# 8_Channel_Relay_Board_Omron.net
KiCad netlist of a schematic drawn in EasyEDA
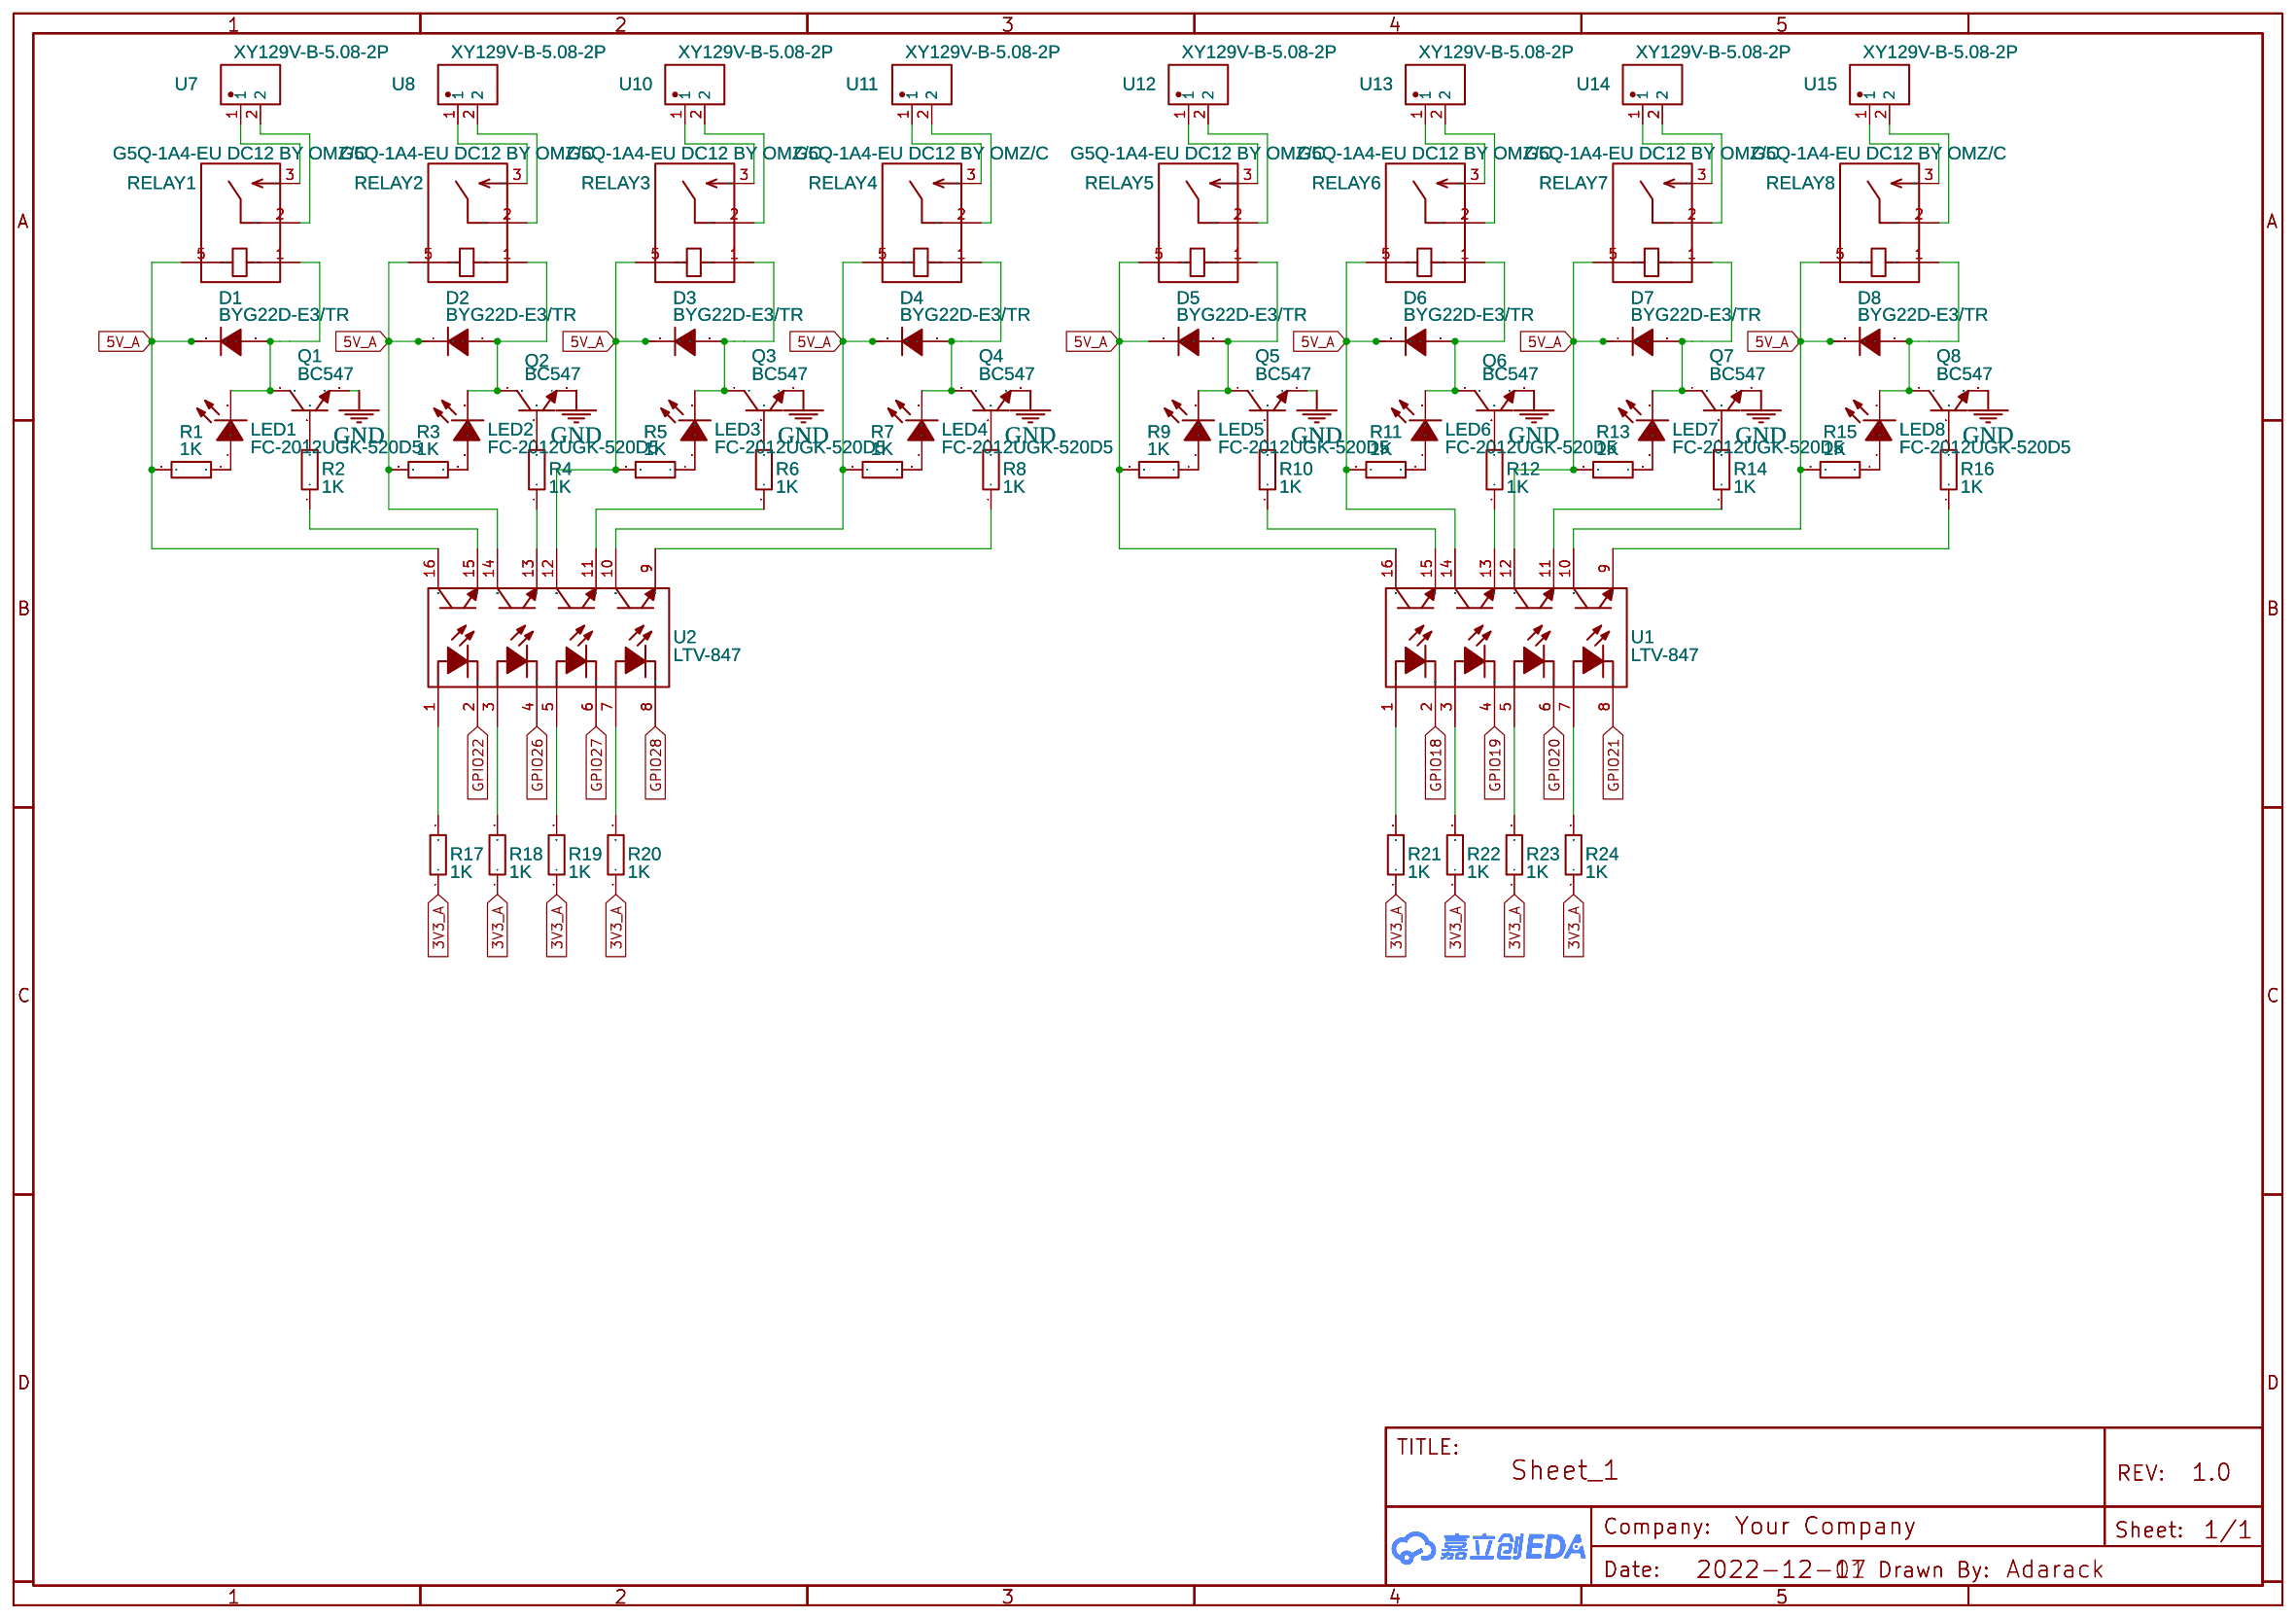
[diagram p0: Relay Section]
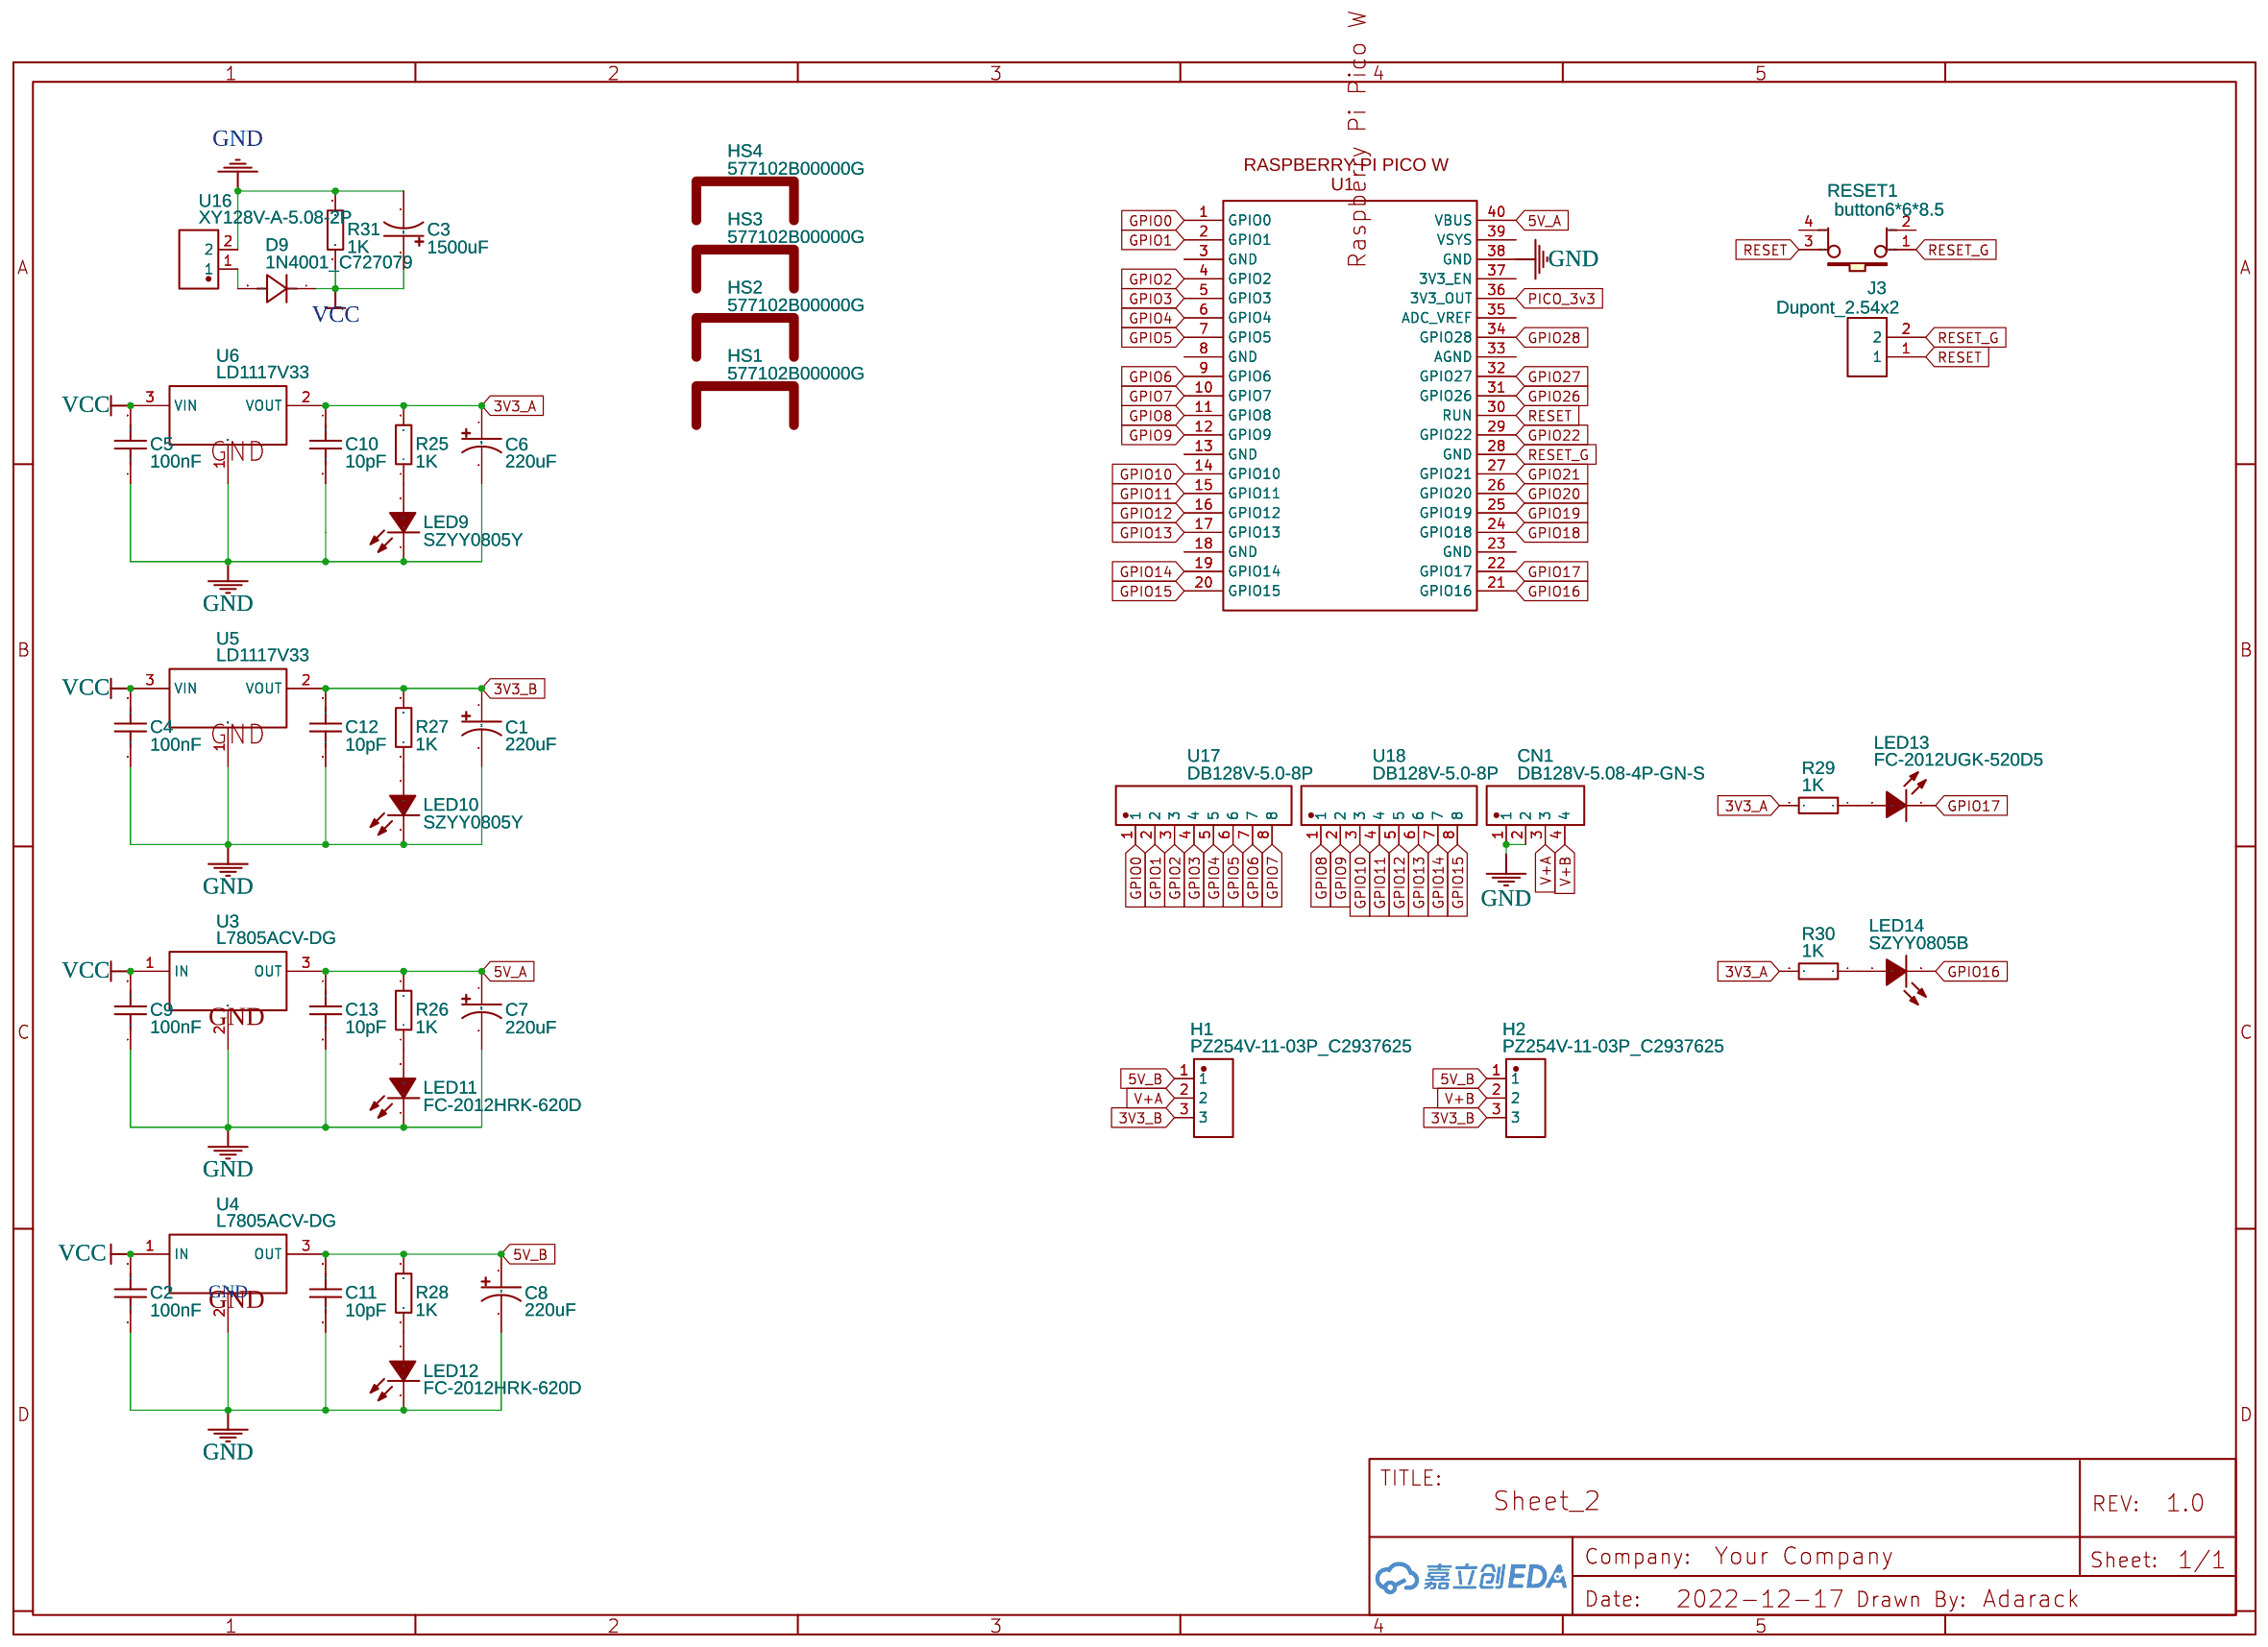
[diagram p1: Pico W Section]

(export (version "E")
  (design (tool "Eeschema 10.0.6"))
  (components
    (comp (ref "D1")
      (value "BYG22D-E3/TR")
      (fields (field (name "BOM_Supplier Part") "C52782"))
      (libsource (lib "") (part "BYG22D-E3/TR"))
    )
    (comp (ref "D2")
      (value "BYG22D-E3/TR")
      (fields (field (name "BOM_Supplier Part") "C52782"))
      (libsource (lib "") (part "BYG22D-E3/TR"))
    )
    (comp (ref "D3")
      (value "BYG22D-E3/TR")
      (fields (field (name "BOM_Supplier Part") "C52782"))
      (libsource (lib "") (part "BYG22D-E3/TR"))
    )
    (comp (ref "D4")
      (value "BYG22D-E3/TR")
      (fields (field (name "BOM_Supplier Part") "C52782"))
      (libsource (lib "") (part "BYG22D-E3/TR"))
    )
    (comp (ref "D5")
      (value "BYG22D-E3/TR")
      (fields (field (name "BOM_Supplier Part") "C52782"))
      (libsource (lib "") (part "BYG22D-E3/TR"))
    )
    (comp (ref "D6")
      (value "BYG22D-E3/TR")
      (fields (field (name "BOM_Supplier Part") "C52782"))
      (libsource (lib "") (part "BYG22D-E3/TR"))
    )
    (comp (ref "D7")
      (value "BYG22D-E3/TR")
      (fields (field (name "BOM_Supplier Part") "C52782"))
      (libsource (lib "") (part "BYG22D-E3/TR"))
    )
    (comp (ref "D8")
      (value "BYG22D-E3/TR")
      (fields (field (name "BOM_Supplier Part") "C52782"))
      (libsource (lib "") (part "BYG22D-E3/TR"))
    )
    (comp (ref "LED1")
      (value "FC-2012UGK-520D5")
      (fields (field (name "BOM_Manufacturer Part") "NCD0805G1") (field (name "BOM_Supplier Part") "C84260"))
      (libsource (lib "") (part "FC-2012UGK-520D5"))
    )
    (comp (ref "LED2")
      (value "FC-2012UGK-520D5")
      (fields (field (name "BOM_Manufacturer Part") "NCD0805G1") (field (name "BOM_Supplier Part") "C84260"))
      (libsource (lib "") (part "FC-2012UGK-520D5"))
    )
    (comp (ref "LED3")
      (value "FC-2012UGK-520D5")
      (fields (field (name "BOM_Manufacturer Part") "NCD0805G1") (field (name "BOM_Supplier Part") "C84260"))
      (libsource (lib "") (part "FC-2012UGK-520D5"))
    )
    (comp (ref "LED4")
      (value "FC-2012UGK-520D5")
      (fields (field (name "BOM_Manufacturer Part") "NCD0805G1") (field (name "BOM_Supplier Part") "C84260"))
      (libsource (lib "") (part "FC-2012UGK-520D5"))
    )
    (comp (ref "LED5")
      (value "FC-2012UGK-520D5")
      (fields (field (name "BOM_Manufacturer Part") "NCD0805G1") (field (name "BOM_Supplier Part") "C84260"))
      (libsource (lib "") (part "FC-2012UGK-520D5"))
    )
    (comp (ref "LED6")
      (value "FC-2012UGK-520D5")
      (fields (field (name "BOM_Manufacturer Part") "NCD0805G1") (field (name "BOM_Supplier Part") "C84260"))
      (libsource (lib "") (part "FC-2012UGK-520D5"))
    )
    (comp (ref "LED7")
      (value "FC-2012UGK-520D5")
      (fields (field (name "BOM_Manufacturer Part") "NCD0805G1") (field (name "BOM_Supplier Part") "C84260"))
      (libsource (lib "") (part "FC-2012UGK-520D5"))
    )
    (comp (ref "LED8")
      (value "FC-2012UGK-520D5")
      (fields (field (name "BOM_Manufacturer Part") "NCD0805G1") (field (name "BOM_Supplier Part") "C84260"))
      (libsource (lib "") (part "FC-2012UGK-520D5"))
    )
    (comp (ref "Q1")
      (value "BC547")
      (fields (field (name "BOM_Supplier Part") "C2910381"))
      (libsource (lib "") (part "BC547"))
    )
    (comp (ref "Q2")
      (value "BC547")
      (fields (field (name "BOM_Supplier Part") "C2910381"))
      (libsource (lib "") (part "BC547"))
    )
    (comp (ref "Q3")
      (value "BC547")
      (fields (field (name "BOM_Supplier Part") "C2910381"))
      (libsource (lib "") (part "BC547"))
    )
    (comp (ref "Q4")
      (value "BC547")
      (fields (field (name "BOM_Supplier Part") "C2910381"))
      (libsource (lib "") (part "BC547"))
    )
    (comp (ref "Q5")
      (value "BC547")
      (fields (field (name "BOM_Supplier Part") "C2910381"))
      (libsource (lib "") (part "BC547"))
    )
    (comp (ref "Q6")
      (value "BC547")
      (fields (field (name "BOM_Supplier Part") "C2910381"))
      (libsource (lib "") (part "BC547"))
    )
    (comp (ref "Q7")
      (value "BC547")
      (fields (field (name "BOM_Supplier Part") "C2910381"))
      (libsource (lib "") (part "BC547"))
    )
    (comp (ref "Q8")
      (value "BC547")
      (fields (field (name "BOM_Supplier Part") "C2910381"))
      (libsource (lib "") (part "BC547"))
    )
    (comp (ref "R1")
      (value "1K")
      (fields
        (field (name "BOM_Manufacturer Part") "RC0805FR-071KL")
        (field (name "BOM_Supplier Part") "C95781")
      )
      (libsource (lib "") (part "RC0805FR-071KL_1"))
    )
    (comp (ref "R2")
      (value "1K")
      (fields
        (field (name "BOM_Manufacturer Part") "RC0805FR-071KL")
        (field (name "BOM_Supplier Part") "C95781")
      )
      (libsource (lib "") (part "RC0805FR-071KL"))
    )
    (comp (ref "R3")
      (value "1K")
      (fields
        (field (name "BOM_Manufacturer Part") "RC0805FR-071KL")
        (field (name "BOM_Supplier Part") "C95781")
      )
      (libsource (lib "") (part "RC0805FR-071KL_1"))
    )
    (comp (ref "R4")
      (value "1K")
      (fields
        (field (name "BOM_Manufacturer Part") "RC0805FR-071KL")
        (field (name "BOM_Supplier Part") "C95781")
      )
      (libsource (lib "") (part "RC0805FR-071KL"))
    )
    (comp (ref "R5")
      (value "1K")
      (fields
        (field (name "BOM_Manufacturer Part") "RC0805FR-071KL")
        (field (name "BOM_Supplier Part") "C95781")
      )
      (libsource (lib "") (part "RC0805FR-071KL_1"))
    )
    (comp (ref "R6")
      (value "1K")
      (fields
        (field (name "BOM_Manufacturer Part") "RC0805FR-071KL")
        (field (name "BOM_Supplier Part") "C95781")
      )
      (libsource (lib "") (part "RC0805FR-071KL"))
    )
    (comp (ref "R7")
      (value "1K")
      (fields
        (field (name "BOM_Manufacturer Part") "RC0805FR-071KL")
        (field (name "BOM_Supplier Part") "C95781")
      )
      (libsource (lib "") (part "RC0805FR-071KL_1"))
    )
    (comp (ref "R8")
      (value "1K")
      (fields
        (field (name "BOM_Manufacturer Part") "RC0805FR-071KL")
        (field (name "BOM_Supplier Part") "C95781")
      )
      (libsource (lib "") (part "RC0805FR-071KL"))
    )
    (comp (ref "R9")
      (value "1K")
      (fields
        (field (name "BOM_Manufacturer Part") "RC0805FR-071KL")
        (field (name "BOM_Supplier Part") "C95781")
      )
      (libsource (lib "") (part "RC0805FR-071KL_1"))
    )
    (comp (ref "R10")
      (value "1K")
      (fields
        (field (name "BOM_Manufacturer Part") "RC0805FR-071KL")
        (field (name "BOM_Supplier Part") "C95781")
      )
      (libsource (lib "") (part "RC0805FR-071KL"))
    )
    (comp (ref "R11")
      (value "1K")
      (fields
        (field (name "BOM_Manufacturer Part") "RC0805FR-071KL")
        (field (name "BOM_Supplier Part") "C95781")
      )
      (libsource (lib "") (part "RC0805FR-071KL_1"))
    )
    (comp (ref "R12")
      (value "1K")
      (fields
        (field (name "BOM_Manufacturer Part") "RC0805FR-071KL")
        (field (name "BOM_Supplier Part") "C95781")
      )
      (libsource (lib "") (part "RC0805FR-071KL"))
    )
    (comp (ref "R13")
      (value "1K")
      (fields
        (field (name "BOM_Manufacturer Part") "RC0805FR-071KL")
        (field (name "BOM_Supplier Part") "C95781")
      )
      (libsource (lib "") (part "RC0805FR-071KL_1"))
    )
    (comp (ref "R14")
      (value "1K")
      (fields
        (field (name "BOM_Manufacturer Part") "RC0805FR-071KL")
        (field (name "BOM_Supplier Part") "C95781")
      )
      (libsource (lib "") (part "RC0805FR-071KL"))
    )
    (comp (ref "R15")
      (value "1K")
      (fields
        (field (name "BOM_Manufacturer Part") "RC0805FR-071KL")
        (field (name "BOM_Supplier Part") "C95781")
      )
      (libsource (lib "") (part "RC0805FR-071KL_1"))
    )
    (comp (ref "R16")
      (value "1K")
      (fields
        (field (name "BOM_Manufacturer Part") "RC0805FR-071KL")
        (field (name "BOM_Supplier Part") "C95781")
      )
      (libsource (lib "") (part "RC0805FR-071KL"))
    )
    (comp (ref "R17")
      (value "1K")
      (fields
        (field (name "BOM_Manufacturer Part") "RC0805FR-071KL")
        (field (name "BOM_Supplier Part") "C95781")
      )
      (libsource (lib "") (part "RC0805FR-071KL"))
    )
    (comp (ref "R18")
      (value "1K")
      (fields
        (field (name "BOM_Manufacturer Part") "RC0805FR-071KL")
        (field (name "BOM_Supplier Part") "C95781")
      )
      (libsource (lib "") (part "RC0805FR-071KL"))
    )
    (comp (ref "R19")
      (value "1K")
      (fields
        (field (name "BOM_Manufacturer Part") "RC0805FR-071KL")
        (field (name "BOM_Supplier Part") "C95781")
      )
      (libsource (lib "") (part "RC0805FR-071KL"))
    )
    (comp (ref "R20")
      (value "1K")
      (fields
        (field (name "BOM_Manufacturer Part") "RC0805FR-071KL")
        (field (name "BOM_Supplier Part") "C95781")
      )
      (libsource (lib "") (part "RC0805FR-071KL"))
    )
    (comp (ref "R21")
      (value "1K")
      (fields
        (field (name "BOM_Manufacturer Part") "RC0805FR-071KL")
        (field (name "BOM_Supplier Part") "C95781")
      )
      (libsource (lib "") (part "RC0805FR-071KL"))
    )
    (comp (ref "R22")
      (value "1K")
      (fields
        (field (name "BOM_Manufacturer Part") "RC0805FR-071KL")
        (field (name "BOM_Supplier Part") "C95781")
      )
      (libsource (lib "") (part "RC0805FR-071KL"))
    )
    (comp (ref "R23")
      (value "1K")
      (fields
        (field (name "BOM_Manufacturer Part") "RC0805FR-071KL")
        (field (name "BOM_Supplier Part") "C95781")
      )
      (libsource (lib "") (part "RC0805FR-071KL"))
    )
    (comp (ref "R24")
      (value "1K")
      (fields
        (field (name "BOM_Manufacturer Part") "RC0805FR-071KL")
        (field (name "BOM_Supplier Part") "C95781")
      )
      (libsource (lib "") (part "RC0805FR-071KL"))
    )
    (comp (ref "RELAY1")
      (value "G5Q-1A4-EU DC12 BY OMZ/C")
      (fields (field (name "BOM_Supplier Part") "C726027"))
      (libsource (lib "") (part "G5Q-1A4-EU DC12 BY OMZ/C"))
    )
    (comp (ref "RELAY2")
      (value "G5Q-1A4-EU DC12 BY OMZ/C")
      (fields (field (name "BOM_Supplier Part") "C726027"))
      (libsource (lib "") (part "G5Q-1A4-EU DC12 BY OMZ/C"))
    )
    (comp (ref "RELAY3")
      (value "G5Q-1A4-EU DC12 BY OMZ/C")
      (fields (field (name "BOM_Supplier Part") "C726027"))
      (libsource (lib "") (part "G5Q-1A4-EU DC12 BY OMZ/C"))
    )
    (comp (ref "RELAY4")
      (value "G5Q-1A4-EU DC12 BY OMZ/C")
      (fields (field (name "BOM_Supplier Part") "C726027"))
      (libsource (lib "") (part "G5Q-1A4-EU DC12 BY OMZ/C"))
    )
    (comp (ref "RELAY5")
      (value "G5Q-1A4-EU DC12 BY OMZ/C")
      (fields (field (name "BOM_Supplier Part") "C726027"))
      (libsource (lib "") (part "G5Q-1A4-EU DC12 BY OMZ/C"))
    )
    (comp (ref "RELAY6")
      (value "G5Q-1A4-EU DC12 BY OMZ/C")
      (fields (field (name "BOM_Supplier Part") "C726027"))
      (libsource (lib "") (part "G5Q-1A4-EU DC12 BY OMZ/C"))
    )
    (comp (ref "RELAY7")
      (value "G5Q-1A4-EU DC12 BY OMZ/C")
      (fields (field (name "BOM_Supplier Part") "C726027"))
      (libsource (lib "") (part "G5Q-1A4-EU DC12 BY OMZ/C"))
    )
    (comp (ref "RELAY8")
      (value "G5Q-1A4-EU DC12 BY OMZ/C")
      (fields (field (name "BOM_Supplier Part") "C726027"))
      (libsource (lib "") (part "G5Q-1A4-EU DC12 BY OMZ/C"))
    )
    (comp (ref "U1")
      (value "LTV-847")
      (fields (field (name "BOM_Supplier Part") "C10794"))
      (libsource (lib "") (part "LTV-847"))
    )
    (comp (ref "U2")
      (value "LTV-847")
      (fields (field (name "BOM_Supplier Part") "C10794"))
      (libsource (lib "") (part "LTV-847"))
    )
    (comp (ref "U7")
      (value "XY129V-B-5.08-2P")
      (fields (field (name "BOM_Supplier Part") "C557671"))
      (libsource (lib "") (part "XY129V-B-5.08-2P"))
    )
    (comp (ref "U8")
      (value "XY129V-B-5.08-2P")
      (fields (field (name "BOM_Supplier Part") "C557671"))
      (libsource (lib "") (part "XY129V-B-5.08-2P"))
    )
    (comp (ref "U10")
      (value "XY129V-B-5.08-2P")
      (fields (field (name "BOM_Supplier Part") "C557671"))
      (libsource (lib "") (part "XY129V-B-5.08-2P"))
    )
    (comp (ref "U11")
      (value "XY129V-B-5.08-2P")
      (fields (field (name "BOM_Supplier Part") "C557671"))
      (libsource (lib "") (part "XY129V-B-5.08-2P"))
    )
    (comp (ref "U12")
      (value "XY129V-B-5.08-2P")
      (fields (field (name "BOM_Supplier Part") "C557671"))
      (libsource (lib "") (part "XY129V-B-5.08-2P"))
    )
    (comp (ref "U13")
      (value "XY129V-B-5.08-2P")
      (fields (field (name "BOM_Supplier Part") "C557671"))
      (libsource (lib "") (part "XY129V-B-5.08-2P"))
    )
    (comp (ref "U14")
      (value "XY129V-B-5.08-2P")
      (fields (field (name "BOM_Supplier Part") "C557671"))
      (libsource (lib "") (part "XY129V-B-5.08-2P"))
    )
    (comp (ref "U15")
      (value "XY129V-B-5.08-2P")
      (fields (field (name "BOM_Supplier Part") "C557671"))
      (libsource (lib "") (part "XY129V-B-5.08-2P"))
    )
    (comp (ref "C1")
      (value "220uF")
      (fields
        (field (name "BOM_Manufacturer Part") "EEUFS0J221")
        (field (name "BOM_Supplier Part") "C407962")
      )
      (libsource (lib "") (part "EEUFS0J221"))
    )
    (comp (ref "C2")
      (value "100nF")
      (fields
        (field (name "BOM_Manufacturer Part") "CC0805KRX7R8BB104")
        (field (name "BOM_Supplier Part") "C519981")
      )
      (libsource (lib "") (part "CC0805KRX7R8BB104"))
    )
    (comp (ref "C3")
      (value "1500uF")
      (fields
        (field (name "BOM_Manufacturer Part") "EGF158M1VI25RRSHP")
        (field (name "BOM_Supplier Part") "C238296")
      )
      (libsource (lib "") (part "EGF158M1VI25RRSHP"))
    )
    (comp (ref "C4")
      (value "100nF")
      (fields
        (field (name "BOM_Manufacturer Part") "CC0805KRX7R8BB104")
        (field (name "BOM_Supplier Part") "C519981")
      )
      (libsource (lib "") (part "CC0805KRX7R8BB104"))
    )
    (comp (ref "C5")
      (value "100nF")
      (fields
        (field (name "BOM_Manufacturer Part") "CC0805KRX7R8BB104")
        (field (name "BOM_Supplier Part") "C519981")
      )
      (libsource (lib "") (part "CC0805KRX7R8BB104"))
    )
    (comp (ref "C6")
      (value "220uF")
      (fields
        (field (name "BOM_Manufacturer Part") "EEUFS0J221")
        (field (name "BOM_Supplier Part") "C407962")
      )
      (libsource (lib "") (part "EEUFS0J221"))
    )
    (comp (ref "C7")
      (value "220uF")
      (fields
        (field (name "BOM_Manufacturer Part") "EEUFS0J221")
        (field (name "BOM_Supplier Part") "C407962")
      )
      (libsource (lib "") (part "EEUFS0J221"))
    )
    (comp (ref "C8")
      (value "220uF")
      (fields
        (field (name "BOM_Manufacturer Part") "EEUFS0J221")
        (field (name "BOM_Supplier Part") "C407962")
      )
      (libsource (lib "") (part "EEUFS0J221_1"))
    )
    (comp (ref "C9")
      (value "100nF")
      (fields
        (field (name "BOM_Manufacturer Part") "CC0805KRX7R8BB104")
        (field (name "BOM_Supplier Part") "C519981")
      )
      (libsource (lib "") (part "CC0805KRX7R8BB104"))
    )
    (comp (ref "C10")
      (value "10pF")
      (fields
        (field (name "BOM_Manufacturer Part") "0805CG100J500NT")
        (field (name "BOM_Supplier Part") "C157608")
      )
      (libsource (lib "") (part "0805CG100J500NT"))
    )
    (comp (ref "C11")
      (value "10pF")
      (fields
        (field (name "BOM_Manufacturer Part") "0805CG100J500NT")
        (field (name "BOM_Supplier Part") "C157608")
      )
      (libsource (lib "") (part "0805CG100J500NT"))
    )
    (comp (ref "C12")
      (value "10pF")
      (fields
        (field (name "BOM_Manufacturer Part") "0805CG100J500NT")
        (field (name "BOM_Supplier Part") "C157608")
      )
      (libsource (lib "") (part "0805CG100J500NT"))
    )
    (comp (ref "C13")
      (value "10pF")
      (fields
        (field (name "BOM_Manufacturer Part") "0805CG100J500NT")
        (field (name "BOM_Supplier Part") "C157608")
      )
      (libsource (lib "") (part "0805CG100J500NT"))
    )
    (comp (ref "CN1")
      (value "DB128V-5.08-4P-GN-S")
      (fields (field (name "BOM_Supplier Part") "C2915641"))
      (libsource (lib "") (part "DB128V-5.08-4P-GN-S"))
    )
    (comp (ref "D9")
      (value "1N4001_C727079")
      (fields (field (name "BOM_Manufacturer Part") "1N4001") (field (name "BOM_Supplier Part") "C727079"))
      (libsource (lib "") (part "1N4001_C727079"))
    )
    (comp (ref "H1")
      (value "PZ254V-11-03P_C2937625")
      (fields
        (field (name "BOM_Manufacturer Part") "PZ254V-11-03P")
        (field (name "BOM_Supplier Part") "C2937625")
      )
      (libsource (lib "") (part "PZ254V-11-03P_C2937625"))
    )
    (comp (ref "H2")
      (value "PZ254V-11-03P_C2937625")
      (fields
        (field (name "BOM_Manufacturer Part") "PZ254V-11-03P")
        (field (name "BOM_Supplier Part") "C2937625")
      )
      (libsource (lib "") (part "PZ254V-11-03P_C2937625"))
    )
    (comp (ref "HS1")
      (value "577102B00000G")
      (fields (field (name "BOM_Supplier Part") "532-577102B00"))
      (libsource (lib "") (part "577102B00000G"))
    )
    (comp (ref "HS2")
      (value "577102B00000G")
      (fields (field (name "BOM_Supplier Part") "532-577102B00"))
      (libsource (lib "") (part "577102B00000G"))
    )
    (comp (ref "HS3")
      (value "577102B00000G")
      (fields (field (name "BOM_Supplier Part") "532-577102B00"))
      (libsource (lib "") (part "577102B00000G"))
    )
    (comp (ref "HS4")
      (value "577102B00000G")
      (fields (field (name "BOM_Supplier Part") "532-577102B00"))
      (libsource (lib "") (part "577102B00000G"))
    )
    (comp (ref "J3") (value "Dupont_2.54x2") (libsource (lib "") (part "Dupont_2.54x2")))
    (comp (ref "LED9")
      (value "SZYY0805Y")
      (fields (field (name "BOM_Supplier Part") "C434436"))
      (libsource (lib "") (part "SZYY0805Y"))
    )
    (comp (ref "LED10")
      (value "SZYY0805Y")
      (fields (field (name "BOM_Supplier Part") "C434436"))
      (libsource (lib "") (part "SZYY0805Y"))
    )
    (comp (ref "LED11")
      (value "FC-2012HRK-620D")
      (fields (field (name "BOM_Supplier Part") "C84256"))
      (libsource (lib "") (part "FC-2012HRK-620D"))
    )
    (comp (ref "LED12")
      (value "FC-2012HRK-620D")
      (fields (field (name "BOM_Supplier Part") "C84256"))
      (libsource (lib "") (part "FC-2012HRK-620D"))
    )
    (comp (ref "LED13")
      (value "FC-2012UGK-520D5")
      (fields (field (name "BOM_Manufacturer Part") "NCD0805G1") (field (name "BOM_Supplier Part") "C84260"))
      (libsource (lib "") (part "FC-2012UGK-520D5"))
    )
    (comp (ref "LED14")
      (value "SZYY0805B")
      (fields (field (name "BOM_Supplier Part") "C434433"))
      (libsource (lib "") (part "SZYY0805B"))
    )
    (comp (ref "R25")
      (value "1K")
      (fields
        (field (name "BOM_Manufacturer Part") "RC0805FR-071KL")
        (field (name "BOM_Supplier Part") "C95781")
      )
      (libsource (lib "") (part "RC0805FR-071KL"))
    )
    (comp (ref "R26")
      (value "1K")
      (fields
        (field (name "BOM_Manufacturer Part") "RC0805FR-071KL")
        (field (name "BOM_Supplier Part") "C95781")
      )
      (libsource (lib "") (part "RC0805FR-071KL"))
    )
    (comp (ref "R27")
      (value "1K")
      (fields
        (field (name "BOM_Manufacturer Part") "RC0805FR-071KL")
        (field (name "BOM_Supplier Part") "C95781")
      )
      (libsource (lib "") (part "RC0805FR-071KL"))
    )
    (comp (ref "R28")
      (value "1K")
      (fields
        (field (name "BOM_Manufacturer Part") "RC0805FR-071KL")
        (field (name "BOM_Supplier Part") "C95781")
      )
      (libsource (lib "") (part "RC0805FR-071KL"))
    )
    (comp (ref "R29")
      (value "1K")
      (fields
        (field (name "BOM_Manufacturer Part") "RC0805FR-071KL")
        (field (name "BOM_Supplier Part") "C95781")
      )
      (libsource (lib "") (part "RC0805FR-071KL_1"))
    )
    (comp (ref "R30")
      (value "1K")
      (fields
        (field (name "BOM_Manufacturer Part") "RC0805FR-071KL")
        (field (name "BOM_Supplier Part") "C95781")
      )
      (libsource (lib "") (part "RC0805FR-071KL_1"))
    )
    (comp (ref "R31")
      (value "1K")
      (fields
        (field (name "BOM_Manufacturer Part") "RC0805FR-071KL")
        (field (name "BOM_Supplier Part") "C95781")
      )
      (libsource (lib "") (part "RC0805FR-071KL"))
    )
    (comp (ref "RESET1")
      (value "button6*6*8.5")
      (fields (field (name "BOM_Supplier Part") "C59980"))
      (libsource (lib "") (part "button6*6*8.5"))
    )
    (comp (ref "U3")
      (value "L7805ACV-DG")
      (fields (field (name "BOM_Supplier Part") "C472632"))
      (libsource (lib "") (part "L7805ACV-DG"))
    )
    (comp (ref "U4")
      (value "L7805ACV-DG")
      (fields (field (name "BOM_Supplier Part") "C472632"))
      (libsource (lib "") (part "L7805ACV-DG"))
    )
    (comp (ref "U5")
      (value "LD1117V33")
      (fields (field (name "BOM_Supplier Part") "C283467"))
      (libsource (lib "") (part "LD1117V33"))
    )
    (comp (ref "U6")
      (value "LD1117V33")
      (fields (field (name "BOM_Supplier Part") "C283467"))
      (libsource (lib "") (part "LD1117V33"))
    )
    (comp (ref "U9") (value "Raspberry Pi Pico W") (libsource (lib "") (part "Raspberry Pi Pico W")))
    (comp (ref "U16")
      (value "XY128V-A-5.08-2P")
      (fields (field (name "BOM_Supplier Part") "C557665"))
      (libsource (lib "") (part "XY128V-A-5.08-2P"))
    )
    (comp (ref "U17")
      (value "DB128V-5.0-8P")
      (fields (field (name "BOM_Supplier Part") "C395863"))
      (libsource (lib "") (part "DB128V-5.0-8P"))
    )
    (comp (ref "U18")
      (value "DB128V-5.0-8P")
      (fields (field (name "BOM_Supplier Part") "C395863"))
      (libsource (lib "") (part "DB128V-5.0-8P"))
    )
  )
  (nets
    (net (code "1") (name "3V3_A") (class "Default")
      (node (ref "C10") (pin "1") (pinfunction "1_1") (pintype "unspecified"))
      (node (ref "C6") (pin "1") (pinfunction "1_1") (pintype "unspecified"))
      (node (ref "R17") (pin "1") (pinfunction "1_1") (pintype "input"))
      (node (ref "R18") (pin "1") (pinfunction "1_1") (pintype "input"))
      (node (ref "R19") (pin "1") (pinfunction "1_1") (pintype "input"))
      (node (ref "R20") (pin "1") (pinfunction "1_1") (pintype "input"))
      (node (ref "R21") (pin "1") (pinfunction "1_1") (pintype "input"))
      (node (ref "R22") (pin "1") (pinfunction "1_1") (pintype "input"))
      (node (ref "R23") (pin "1") (pinfunction "1_1") (pintype "input"))
      (node (ref "R24") (pin "1") (pinfunction "1_1") (pintype "input"))
      (node (ref "R25") (pin "2") (pinfunction "2_2") (pintype "input"))
      (node (ref "R29") (pin "2") (pinfunction "2_2") (pintype "input"))
      (node (ref "R30") (pin "2") (pinfunction "2_2") (pintype "input"))
      (node (ref "U6") (pin "2") (pinfunction "VOUT_2") (pintype "passive"))
    )
    (net (code "2") (name "3V3_B") (class "Default")
      (node (ref "C1") (pin "1") (pinfunction "1_1") (pintype "unspecified"))
      (node (ref "C12") (pin "1") (pinfunction "1_1") (pintype "unspecified"))
      (node (ref "H1") (pin "3") (pinfunction "3_3") (pintype "unspecified"))
      (node (ref "H2") (pin "3") (pinfunction "3_3") (pintype "unspecified"))
      (node (ref "R27") (pin "2") (pinfunction "2_2") (pintype "input"))
      (node (ref "U5") (pin "2") (pinfunction "VOUT_2") (pintype "passive"))
    )
    (net (code "3") (name "5V_A") (class "Default")
      (node (ref "C13") (pin "1") (pinfunction "1_1") (pintype "unspecified"))
      (node (ref "C7") (pin "1") (pinfunction "1_1") (pintype "unspecified"))
      (node (ref "D1") (pin "1") (pinfunction "K_1") (pintype "unspecified"))
      (node (ref "D2") (pin "1") (pinfunction "K_1") (pintype "unspecified"))
      (node (ref "D3") (pin "1") (pinfunction "K_1") (pintype "unspecified"))
      (node (ref "D4") (pin "1") (pinfunction "K_1") (pintype "unspecified"))
      (node (ref "D5") (pin "1") (pinfunction "K_1") (pintype "unspecified"))
      (node (ref "D6") (pin "1") (pinfunction "K_1") (pintype "unspecified"))
      (node (ref "D7") (pin "1") (pinfunction "K_1") (pintype "unspecified"))
      (node (ref "D8") (pin "1") (pinfunction "K_1") (pintype "unspecified"))
      (node (ref "R1") (pin "2") (pinfunction "2_2") (pintype "input"))
      (node (ref "R11") (pin "2") (pinfunction "2_2") (pintype "input"))
      (node (ref "R13") (pin "2") (pinfunction "2_2") (pintype "input"))
      (node (ref "R15") (pin "2") (pinfunction "2_2") (pintype "input"))
      (node (ref "R26") (pin "2") (pinfunction "2_2") (pintype "input"))
      (node (ref "R3") (pin "2") (pinfunction "2_2") (pintype "input"))
      (node (ref "R5") (pin "2") (pinfunction "2_2") (pintype "input"))
      (node (ref "R7") (pin "2") (pinfunction "2_2") (pintype "input"))
      (node (ref "R9") (pin "2") (pinfunction "2_2") (pintype "input"))
      (node (ref "RELAY1") (pin "5") (pinfunction "5_5") (pintype "unspecified"))
      (node (ref "RELAY2") (pin "5") (pinfunction "5_5") (pintype "unspecified"))
      (node (ref "RELAY3") (pin "5") (pinfunction "5_5") (pintype "unspecified"))
      (node (ref "RELAY4") (pin "5") (pinfunction "5_5") (pintype "unspecified"))
      (node (ref "RELAY5") (pin "5") (pinfunction "5_5") (pintype "unspecified"))
      (node (ref "RELAY6") (pin "5") (pinfunction "5_5") (pintype "unspecified"))
      (node (ref "RELAY7") (pin "5") (pinfunction "5_5") (pintype "unspecified"))
      (node (ref "RELAY8") (pin "5") (pinfunction "5_5") (pintype "unspecified"))
      (node (ref "U1") (pin "10") (pinfunction "COL_10") (pintype "unspecified"))
      (node (ref "U1") (pin "12") (pinfunction "COL_12") (pintype "unspecified"))
      (node (ref "U1") (pin "14") (pinfunction "COL_14") (pintype "unspecified"))
      (node (ref "U1") (pin "16") (pinfunction "COL_16") (pintype "unspecified"))
      (node (ref "U2") (pin "10") (pinfunction "COL_10") (pintype "unspecified"))
      (node (ref "U2") (pin "12") (pinfunction "COL_12") (pintype "unspecified"))
      (node (ref "U2") (pin "14") (pinfunction "COL_14") (pintype "unspecified"))
      (node (ref "U2") (pin "16") (pinfunction "COL_16") (pintype "unspecified"))
      (node (ref "U3") (pin "3") (pinfunction "OUT_3") (pintype "passive"))
      (node (ref "U9") (pin "40") (pinfunction "VBUS_40") (pintype "unspecified"))
    )
    (net (code "4") (name "5V_B") (class "Default")
      (node (ref "C11") (pin "1") (pinfunction "1_1") (pintype "unspecified"))
      (node (ref "C8") (pin "1") (pinfunction "1_1") (pintype "unspecified"))
      (node (ref "H1") (pin "1") (pinfunction "1_1") (pintype "unspecified"))
      (node (ref "H2") (pin "1") (pinfunction "1_1") (pintype "unspecified"))
      (node (ref "R28") (pin "2") (pinfunction "2_2") (pintype "input"))
      (node (ref "U4") (pin "3") (pinfunction "OUT_3") (pintype "passive"))
    )
    (net (code "5") (name "GND") (class "Default")
      (node (ref "C1") (pin "2") (pinfunction "2_2") (pintype "unspecified"))
      (node (ref "C10") (pin "2") (pinfunction "2_2") (pintype "unspecified"))
      (node (ref "C11") (pin "2") (pinfunction "2_2") (pintype "unspecified"))
      (node (ref "C12") (pin "2") (pinfunction "2_2") (pintype "unspecified"))
      (node (ref "C13") (pin "2") (pinfunction "2_2") (pintype "unspecified"))
      (node (ref "C2") (pin "1") (pinfunction "1_1") (pintype "unspecified"))
      (node (ref "C3") (pin "2") (pinfunction "2_2") (pintype "unspecified"))
      (node (ref "C4") (pin "1") (pinfunction "1_1") (pintype "unspecified"))
      (node (ref "C5") (pin "1") (pinfunction "1_1") (pintype "unspecified"))
      (node (ref "C6") (pin "2") (pinfunction "2_2") (pintype "unspecified"))
      (node (ref "C7") (pin "2") (pinfunction "2_2") (pintype "unspecified"))
      (node (ref "C8") (pin "2") (pinfunction "2_2") (pintype "unspecified"))
      (node (ref "C9") (pin "1") (pinfunction "1_1") (pintype "unspecified"))
      (node (ref "CN1") (pin "1") (pinfunction "1_1") (pintype "unspecified"))
      (node (ref "CN1") (pin "2") (pinfunction "2_2") (pintype "unspecified"))
      (node (ref "LED10") (pin "1") (pinfunction "-_1") (pintype "unspecified"))
      (node (ref "LED11") (pin "1") (pinfunction "-_1") (pintype "unspecified"))
      (node (ref "LED12") (pin "1") (pinfunction "-_1") (pintype "unspecified"))
      (node (ref "LED9") (pin "1") (pinfunction "-_1") (pintype "unspecified"))
      (node (ref "Q1") (pin "3") (pinfunction "E_3") (pintype "unspecified"))
      (node (ref "Q2") (pin "3") (pinfunction "E_3") (pintype "unspecified"))
      (node (ref "Q3") (pin "3") (pinfunction "E_3") (pintype "unspecified"))
      (node (ref "Q4") (pin "3") (pinfunction "E_3") (pintype "unspecified"))
      (node (ref "Q5") (pin "3") (pinfunction "E_3") (pintype "unspecified"))
      (node (ref "Q6") (pin "3") (pinfunction "E_3") (pintype "unspecified"))
      (node (ref "Q7") (pin "3") (pinfunction "E_3") (pintype "unspecified"))
      (node (ref "Q8") (pin "3") (pinfunction "E_3") (pintype "unspecified"))
      (node (ref "R31") (pin "2") (pinfunction "2_2") (pintype "input"))
      (node (ref "U16") (pin "2") (pinfunction "2_2") (pintype "unspecified"))
      (node (ref "U3") (pin "2") (pinfunction "GND_2") (pintype "passive"))
      (node (ref "U4") (pin "2") (pinfunction "GND_2") (pintype "passive"))
      (node (ref "U5") (pin "1") (pinfunction "GND_1") (pintype "unspecified"))
      (node (ref "U6") (pin "1") (pinfunction "GND_1") (pintype "unspecified"))
      (node (ref "U9") (pin "38") (pinfunction "GND_38") (pintype "unspecified"))
    )
    (net (code "6") (name "GPIO0") (class "Default")
      (node (ref "U17") (pin "1") (pinfunction "1_1") (pintype "unspecified"))
      (node (ref "U9") (pin "1") (pinfunction "GPIO0_1") (pintype "unspecified"))
    )
    (net (code "7") (name "GPIO1") (class "Default")
      (node (ref "U17") (pin "2") (pinfunction "2_2") (pintype "unspecified"))
      (node (ref "U9") (pin "2") (pinfunction "GPIO1_2") (pintype "unspecified"))
    )
    (net (code "8") (name "GPIO2") (class "Default")
      (node (ref "U17") (pin "3") (pinfunction "3_3") (pintype "unspecified"))
      (node (ref "U9") (pin "4") (pinfunction "GPIO2_4") (pintype "unspecified"))
    )
    (net (code "9") (name "GPIO3") (class "Default")
      (node (ref "U17") (pin "4") (pinfunction "4_4") (pintype "unspecified"))
      (node (ref "U9") (pin "5") (pinfunction "GPIO3_5") (pintype "unspecified"))
    )
    (net (code "10") (name "GPIO4") (class "Default")
      (node (ref "U17") (pin "5") (pinfunction "5_5") (pintype "unspecified"))
      (node (ref "U9") (pin "6") (pinfunction "GPIO4_6") (pintype "unspecified"))
    )
    (net (code "11") (name "GPIO5") (class "Default")
      (node (ref "U17") (pin "6") (pinfunction "6_6") (pintype "unspecified"))
      (node (ref "U9") (pin "7") (pinfunction "GPIO5_7") (pintype "unspecified"))
    )
    (net (code "12") (name "GPIO6") (class "Default")
      (node (ref "U17") (pin "7") (pinfunction "7_7") (pintype "unspecified"))
      (node (ref "U9") (pin "9") (pinfunction "GPIO6_9") (pintype "unspecified"))
    )
    (net (code "13") (name "GPIO7") (class "Default")
      (node (ref "U17") (pin "8") (pinfunction "8_8") (pintype "unspecified"))
      (node (ref "U9") (pin "10") (pinfunction "GPIO7_10") (pintype "unspecified"))
    )
    (net (code "14") (name "GPIO8") (class "Default")
      (node (ref "U18") (pin "1") (pinfunction "1_1") (pintype "unspecified"))
      (node (ref "U9") (pin "11") (pinfunction "GPIO8_11") (pintype "unspecified"))
    )
    (net (code "15") (name "GPIO9") (class "Default")
      (node (ref "U18") (pin "2") (pinfunction "2_2") (pintype "unspecified"))
      (node (ref "U9") (pin "12") (pinfunction "GPIO9_12") (pintype "unspecified"))
    )
    (net (code "16") (name "GPIO10") (class "Default")
      (node (ref "U18") (pin "3") (pinfunction "3_3") (pintype "unspecified"))
      (node (ref "U9") (pin "14") (pinfunction "GPIO10_14") (pintype "unspecified"))
    )
    (net (code "17") (name "GPIO11") (class "Default")
      (node (ref "U18") (pin "4") (pinfunction "4_4") (pintype "unspecified"))
      (node (ref "U9") (pin "15") (pinfunction "GPIO11_15") (pintype "unspecified"))
    )
    (net (code "18") (name "GPIO12") (class "Default")
      (node (ref "U18") (pin "5") (pinfunction "5_5") (pintype "unspecified"))
      (node (ref "U9") (pin "16") (pinfunction "GPIO12_16") (pintype "unspecified"))
    )
    (net (code "19") (name "GPIO13") (class "Default")
      (node (ref "U18") (pin "6") (pinfunction "6_6") (pintype "unspecified"))
      (node (ref "U9") (pin "17") (pinfunction "GPIO13_17") (pintype "unspecified"))
    )
    (net (code "20") (name "GPIO14") (class "Default")
      (node (ref "U18") (pin "7") (pinfunction "7_7") (pintype "unspecified"))
      (node (ref "U9") (pin "19") (pinfunction "GPIO14_19") (pintype "unspecified"))
    )
    (net (code "21") (name "GPIO15") (class "Default")
      (node (ref "U18") (pin "8") (pinfunction "8_8") (pintype "unspecified"))
      (node (ref "U9") (pin "20") (pinfunction "GPIO15_20") (pintype "unspecified"))
    )
    (net (code "22") (name "GPIO16") (class "Default")
      (node (ref "LED14") (pin "2") (pinfunction "-_2") (pintype "unspecified"))
      (node (ref "U9") (pin "21") (pinfunction "GPIO16_21") (pintype "unspecified"))
    )
    (net (code "23") (name "GPIO17") (class "Default")
      (node (ref "LED13") (pin "2") (pinfunction "K_2") (pintype "unspecified"))
      (node (ref "U9") (pin "22") (pinfunction "GPIO17_22") (pintype "unspecified"))
    )
    (net (code "24") (name "GPIO18") (class "Default")
      (node (ref "U1") (pin "2") (pinfunction "CAT_2") (pintype "unspecified"))
      (node (ref "U9") (pin "24") (pinfunction "GPIO18_24") (pintype "unspecified"))
    )
    (net (code "25") (name "GPIO19") (class "Default")
      (node (ref "U1") (pin "4") (pinfunction "CAT_4") (pintype "unspecified"))
      (node (ref "U9") (pin "25") (pinfunction "GPIO19_25") (pintype "unspecified"))
    )
    (net (code "26") (name "GPIO20") (class "Default")
      (node (ref "U1") (pin "6") (pinfunction "CAT_6") (pintype "unspecified"))
      (node (ref "U9") (pin "26") (pinfunction "GPIO20_26") (pintype "unspecified"))
    )
    (net (code "27") (name "GPIO21") (class "Default")
      (node (ref "U1") (pin "8") (pinfunction "CAT_8") (pintype "unspecified"))
      (node (ref "U9") (pin "27") (pinfunction "GPIO21_27") (pintype "unspecified"))
    )
    (net (code "28") (name "GPIO22") (class "Default")
      (node (ref "U2") (pin "2") (pinfunction "CAT_2") (pintype "unspecified"))
      (node (ref "U9") (pin "29") (pinfunction "GPIO22_29") (pintype "unspecified"))
    )
    (net (code "29") (name "GPIO26") (class "Default")
      (node (ref "U2") (pin "4") (pinfunction "CAT_4") (pintype "unspecified"))
      (node (ref "U9") (pin "31") (pinfunction "GPIO26_31") (pintype "unspecified"))
    )
    (net (code "30") (name "GPIO27") (class "Default")
      (node (ref "U2") (pin "6") (pinfunction "CAT_6") (pintype "unspecified"))
      (node (ref "U9") (pin "32") (pinfunction "GPIO27_32") (pintype "unspecified"))
    )
    (net (code "31") (name "GPIO28") (class "Default")
      (node (ref "U2") (pin "8") (pinfunction "CAT_8") (pintype "unspecified"))
      (node (ref "U9") (pin "34") (pinfunction "GPIO28_34") (pintype "unspecified"))
    )
    (net (code "32") (name "Net-(D1-A)") (class "Default")
      (node (ref "D1") (pin "2") (pinfunction "A_2") (pintype "unspecified"))
      (node (ref "LED1") (pin "2") (pinfunction "K_2") (pintype "unspecified"))
      (node (ref "Q1") (pin "1") (pinfunction "C_1") (pintype "unspecified"))
      (node (ref "RELAY1") (pin "1") (pinfunction "1_1") (pintype "unspecified"))
    )
    (net (code "33") (name "Net-(D2-A)") (class "Default")
      (node (ref "D2") (pin "2") (pinfunction "A_2") (pintype "unspecified"))
      (node (ref "LED2") (pin "2") (pinfunction "K_2") (pintype "unspecified"))
      (node (ref "Q2") (pin "1") (pinfunction "C_1") (pintype "unspecified"))
      (node (ref "RELAY2") (pin "1") (pinfunction "1_1") (pintype "unspecified"))
    )
    (net (code "34") (name "Net-(D3-A)") (class "Default")
      (node (ref "D3") (pin "2") (pinfunction "A_2") (pintype "unspecified"))
      (node (ref "LED3") (pin "2") (pinfunction "K_2") (pintype "unspecified"))
      (node (ref "Q3") (pin "1") (pinfunction "C_1") (pintype "unspecified"))
      (node (ref "RELAY3") (pin "1") (pinfunction "1_1") (pintype "unspecified"))
    )
    (net (code "35") (name "Net-(D4-A)") (class "Default")
      (node (ref "D4") (pin "2") (pinfunction "A_2") (pintype "unspecified"))
      (node (ref "LED4") (pin "2") (pinfunction "K_2") (pintype "unspecified"))
      (node (ref "Q4") (pin "1") (pinfunction "C_1") (pintype "unspecified"))
      (node (ref "RELAY4") (pin "1") (pinfunction "1_1") (pintype "unspecified"))
    )
    (net (code "36") (name "Net-(D5-A)") (class "Default")
      (node (ref "D5") (pin "2") (pinfunction "A_2") (pintype "unspecified"))
      (node (ref "LED5") (pin "2") (pinfunction "K_2") (pintype "unspecified"))
      (node (ref "Q5") (pin "1") (pinfunction "C_1") (pintype "unspecified"))
      (node (ref "RELAY5") (pin "1") (pinfunction "1_1") (pintype "unspecified"))
    )
    (net (code "37") (name "Net-(D6-A)") (class "Default")
      (node (ref "D6") (pin "2") (pinfunction "A_2") (pintype "unspecified"))
      (node (ref "LED6") (pin "2") (pinfunction "K_2") (pintype "unspecified"))
      (node (ref "Q6") (pin "1") (pinfunction "C_1") (pintype "unspecified"))
      (node (ref "RELAY6") (pin "1") (pinfunction "1_1") (pintype "unspecified"))
    )
    (net (code "38") (name "Net-(D7-A)") (class "Default")
      (node (ref "D7") (pin "2") (pinfunction "A_2") (pintype "unspecified"))
      (node (ref "LED7") (pin "2") (pinfunction "K_2") (pintype "unspecified"))
      (node (ref "Q7") (pin "1") (pinfunction "C_1") (pintype "unspecified"))
      (node (ref "RELAY7") (pin "1") (pinfunction "1_1") (pintype "unspecified"))
    )
    (net (code "39") (name "Net-(D8-A)") (class "Default")
      (node (ref "D8") (pin "2") (pinfunction "A_2") (pintype "unspecified"))
      (node (ref "LED8") (pin "2") (pinfunction "K_2") (pintype "unspecified"))
      (node (ref "Q8") (pin "1") (pinfunction "C_1") (pintype "unspecified"))
      (node (ref "RELAY8") (pin "1") (pinfunction "1_1") (pintype "unspecified"))
    )
    (net (code "40") (name "Net-(D9-A)") (class "Default")
      (node (ref "D9") (pin "2") (pinfunction "A_2") (pintype "unspecified"))
      (node (ref "U16") (pin "1") (pinfunction "1_1") (pintype "unspecified"))
    )
    (net (code "41") (name "Net-(LED1-A)") (class "Default")
      (node (ref "LED1") (pin "1") (pinfunction "A_1") (pintype "unspecified"))
      (node (ref "R1") (pin "1") (pinfunction "1_1") (pintype "input"))
    )
    (net (code "42") (name "Net-(LED2-A)") (class "Default")
      (node (ref "LED2") (pin "1") (pinfunction "A_1") (pintype "unspecified"))
      (node (ref "R3") (pin "1") (pinfunction "1_1") (pintype "input"))
    )
    (net (code "43") (name "Net-(LED3-A)") (class "Default")
      (node (ref "LED3") (pin "1") (pinfunction "A_1") (pintype "unspecified"))
      (node (ref "R5") (pin "1") (pinfunction "1_1") (pintype "input"))
    )
    (net (code "44") (name "Net-(LED4-A)") (class "Default")
      (node (ref "LED4") (pin "1") (pinfunction "A_1") (pintype "unspecified"))
      (node (ref "R7") (pin "1") (pinfunction "1_1") (pintype "input"))
    )
    (net (code "45") (name "Net-(LED5-A)") (class "Default")
      (node (ref "LED5") (pin "1") (pinfunction "A_1") (pintype "unspecified"))
      (node (ref "R9") (pin "1") (pinfunction "1_1") (pintype "input"))
    )
    (net (code "46") (name "Net-(LED6-A)") (class "Default")
      (node (ref "LED6") (pin "1") (pinfunction "A_1") (pintype "unspecified"))
      (node (ref "R11") (pin "1") (pinfunction "1_1") (pintype "input"))
    )
    (net (code "47") (name "Net-(LED7-A)") (class "Default")
      (node (ref "LED7") (pin "1") (pinfunction "A_1") (pintype "unspecified"))
      (node (ref "R13") (pin "1") (pinfunction "1_1") (pintype "input"))
    )
    (net (code "48") (name "Net-(LED8-A)") (class "Default")
      (node (ref "LED8") (pin "1") (pinfunction "A_1") (pintype "unspecified"))
      (node (ref "R15") (pin "1") (pinfunction "1_1") (pintype "input"))
    )
    (net (code "49") (name "Net-(LED9-+)") (class "Default")
      (node (ref "LED9") (pin "2") (pinfunction "+_2") (pintype "unspecified"))
      (node (ref "R25") (pin "1") (pinfunction "1_1") (pintype "input"))
    )
    (net (code "50") (name "Net-(LED10-+)") (class "Default")
      (node (ref "LED10") (pin "2") (pinfunction "+_2") (pintype "unspecified"))
      (node (ref "R27") (pin "1") (pinfunction "1_1") (pintype "input"))
    )
    (net (code "51") (name "Net-(LED11-+)") (class "Default")
      (node (ref "LED11") (pin "2") (pinfunction "+_2") (pintype "unspecified"))
      (node (ref "R26") (pin "1") (pinfunction "1_1") (pintype "input"))
    )
    (net (code "52") (name "Net-(LED12-+)") (class "Default")
      (node (ref "LED12") (pin "2") (pinfunction "+_2") (pintype "unspecified"))
      (node (ref "R28") (pin "1") (pinfunction "1_1") (pintype "input"))
    )
    (net (code "53") (name "Net-(LED13-A)") (class "Default")
      (node (ref "LED13") (pin "1") (pinfunction "A_1") (pintype "unspecified"))
      (node (ref "R29") (pin "1") (pinfunction "1_1") (pintype "input"))
    )
    (net (code "54") (name "Net-(LED14-+)") (class "Default")
      (node (ref "LED14") (pin "1") (pinfunction "+_1") (pintype "unspecified"))
      (node (ref "R30") (pin "1") (pinfunction "1_1") (pintype "input"))
    )
    (net (code "55") (name "Net-(Q1-B)") (class "Default")
      (node (ref "Q1") (pin "2") (pinfunction "B_2") (pintype "unspecified"))
      (node (ref "R2") (pin "2") (pinfunction "2_2") (pintype "input"))
    )
    (net (code "56") (name "Net-(Q2-B)") (class "Default")
      (node (ref "Q2") (pin "2") (pinfunction "B_2") (pintype "unspecified"))
      (node (ref "R4") (pin "2") (pinfunction "2_2") (pintype "input"))
    )
    (net (code "57") (name "Net-(Q3-B)") (class "Default")
      (node (ref "Q3") (pin "2") (pinfunction "B_2") (pintype "unspecified"))
      (node (ref "R6") (pin "2") (pinfunction "2_2") (pintype "input"))
    )
    (net (code "58") (name "Net-(Q4-B)") (class "Default")
      (node (ref "Q4") (pin "2") (pinfunction "B_2") (pintype "unspecified"))
      (node (ref "R8") (pin "2") (pinfunction "2_2") (pintype "input"))
    )
    (net (code "59") (name "Net-(Q5-B)") (class "Default")
      (node (ref "Q5") (pin "2") (pinfunction "B_2") (pintype "unspecified"))
      (node (ref "R10") (pin "2") (pinfunction "2_2") (pintype "input"))
    )
    (net (code "60") (name "Net-(Q6-B)") (class "Default")
      (node (ref "Q6") (pin "2") (pinfunction "B_2") (pintype "unspecified"))
      (node (ref "R12") (pin "2") (pinfunction "2_2") (pintype "input"))
    )
    (net (code "61") (name "Net-(Q7-B)") (class "Default")
      (node (ref "Q7") (pin "2") (pinfunction "B_2") (pintype "unspecified"))
      (node (ref "R14") (pin "2") (pinfunction "2_2") (pintype "input"))
    )
    (net (code "62") (name "Net-(Q8-B)") (class "Default")
      (node (ref "Q8") (pin "2") (pinfunction "B_2") (pintype "unspecified"))
      (node (ref "R16") (pin "2") (pinfunction "2_2") (pintype "input"))
    )
    (net (code "63") (name "Net-(R2-Pad1)") (class "Default")
      (node (ref "R2") (pin "1") (pinfunction "1_1") (pintype "input"))
      (node (ref "U2") (pin "15") (pinfunction "EM_15") (pintype "unspecified"))
    )
    (net (code "64") (name "Net-(R4-Pad1)") (class "Default")
      (node (ref "R4") (pin "1") (pinfunction "1_1") (pintype "input"))
      (node (ref "U2") (pin "13") (pinfunction "EM_13") (pintype "unspecified"))
    )
    (net (code "65") (name "Net-(R6-Pad1)") (class "Default")
      (node (ref "R6") (pin "1") (pinfunction "1_1") (pintype "input"))
      (node (ref "U2") (pin "11") (pinfunction "EM_11") (pintype "unspecified"))
    )
    (net (code "66") (name "Net-(R8-Pad1)") (class "Default")
      (node (ref "R8") (pin "1") (pinfunction "1_1") (pintype "input"))
      (node (ref "U2") (pin "9") (pinfunction "EM_9") (pintype "unspecified"))
    )
    (net (code "67") (name "Net-(R10-Pad1)") (class "Default")
      (node (ref "R10") (pin "1") (pinfunction "1_1") (pintype "input"))
      (node (ref "U1") (pin "15") (pinfunction "EM_15") (pintype "unspecified"))
    )
    (net (code "68") (name "Net-(R12-Pad1)") (class "Default")
      (node (ref "R12") (pin "1") (pinfunction "1_1") (pintype "input"))
      (node (ref "U1") (pin "13") (pinfunction "EM_13") (pintype "unspecified"))
    )
    (net (code "69") (name "Net-(R14-Pad1)") (class "Default")
      (node (ref "R14") (pin "1") (pinfunction "1_1") (pintype "input"))
      (node (ref "U1") (pin "11") (pinfunction "EM_11") (pintype "unspecified"))
    )
    (net (code "70") (name "Net-(R16-Pad1)") (class "Default")
      (node (ref "R16") (pin "1") (pinfunction "1_1") (pintype "input"))
      (node (ref "U1") (pin "9") (pinfunction "EM_9") (pintype "unspecified"))
    )
    (net (code "71") (name "Net-(R17-Pad2)") (class "Default")
      (node (ref "R17") (pin "2") (pinfunction "2_2") (pintype "input"))
      (node (ref "U2") (pin "1") (pinfunction "AN_1") (pintype "unspecified"))
    )
    (net (code "72") (name "Net-(R18-Pad2)") (class "Default")
      (node (ref "R18") (pin "2") (pinfunction "2_2") (pintype "input"))
      (node (ref "U2") (pin "3") (pinfunction "AN_3") (pintype "unspecified"))
    )
    (net (code "73") (name "Net-(R19-Pad2)") (class "Default")
      (node (ref "R19") (pin "2") (pinfunction "2_2") (pintype "input"))
      (node (ref "U2") (pin "5") (pinfunction "AN_5") (pintype "unspecified"))
    )
    (net (code "74") (name "Net-(R20-Pad2)") (class "Default")
      (node (ref "R20") (pin "2") (pinfunction "2_2") (pintype "input"))
      (node (ref "U2") (pin "7") (pinfunction "AN_7") (pintype "unspecified"))
    )
    (net (code "75") (name "Net-(R21-Pad2)") (class "Default")
      (node (ref "R21") (pin "2") (pinfunction "2_2") (pintype "input"))
      (node (ref "U1") (pin "1") (pinfunction "AN_1") (pintype "unspecified"))
    )
    (net (code "76") (name "Net-(R22-Pad2)") (class "Default")
      (node (ref "R22") (pin "2") (pinfunction "2_2") (pintype "input"))
      (node (ref "U1") (pin "3") (pinfunction "AN_3") (pintype "unspecified"))
    )
    (net (code "77") (name "Net-(R23-Pad2)") (class "Default")
      (node (ref "R23") (pin "2") (pinfunction "2_2") (pintype "input"))
      (node (ref "U1") (pin "5") (pinfunction "AN_5") (pintype "unspecified"))
    )
    (net (code "78") (name "Net-(R24-Pad2)") (class "Default")
      (node (ref "R24") (pin "2") (pinfunction "2_2") (pintype "input"))
      (node (ref "U1") (pin "7") (pinfunction "AN_7") (pintype "unspecified"))
    )
    (net (code "79") (name "Net-(RELAY1-Pad2)") (class "Default")
      (node (ref "RELAY1") (pin "2") (pinfunction "2_2") (pintype "unspecified"))
      (node (ref "U7") (pin "2") (pinfunction "2_2") (pintype "unspecified"))
    )
    (net (code "80") (name "Net-(RELAY1-Pad3)") (class "Default")
      (node (ref "RELAY1") (pin "3") (pinfunction "3_3") (pintype "unspecified"))
      (node (ref "U7") (pin "1") (pinfunction "1_1") (pintype "unspecified"))
    )
    (net (code "81") (name "Net-(RELAY2-Pad2)") (class "Default")
      (node (ref "RELAY2") (pin "2") (pinfunction "2_2") (pintype "unspecified"))
      (node (ref "U8") (pin "2") (pinfunction "2_2") (pintype "unspecified"))
    )
    (net (code "82") (name "Net-(RELAY2-Pad3)") (class "Default")
      (node (ref "RELAY2") (pin "3") (pinfunction "3_3") (pintype "unspecified"))
      (node (ref "U8") (pin "1") (pinfunction "1_1") (pintype "unspecified"))
    )
    (net (code "83") (name "Net-(RELAY3-Pad2)") (class "Default")
      (node (ref "RELAY3") (pin "2") (pinfunction "2_2") (pintype "unspecified"))
      (node (ref "U10") (pin "2") (pinfunction "2_2") (pintype "unspecified"))
    )
    (net (code "84") (name "Net-(RELAY3-Pad3)") (class "Default")
      (node (ref "RELAY3") (pin "3") (pinfunction "3_3") (pintype "unspecified"))
      (node (ref "U10") (pin "1") (pinfunction "1_1") (pintype "unspecified"))
    )
    (net (code "85") (name "Net-(RELAY4-Pad2)") (class "Default")
      (node (ref "RELAY4") (pin "2") (pinfunction "2_2") (pintype "unspecified"))
      (node (ref "U11") (pin "2") (pinfunction "2_2") (pintype "unspecified"))
    )
    (net (code "86") (name "Net-(RELAY4-Pad3)") (class "Default")
      (node (ref "RELAY4") (pin "3") (pinfunction "3_3") (pintype "unspecified"))
      (node (ref "U11") (pin "1") (pinfunction "1_1") (pintype "unspecified"))
    )
    (net (code "87") (name "Net-(RELAY5-Pad2)") (class "Default")
      (node (ref "RELAY5") (pin "2") (pinfunction "2_2") (pintype "unspecified"))
      (node (ref "U12") (pin "2") (pinfunction "2_2") (pintype "unspecified"))
    )
    (net (code "88") (name "Net-(RELAY5-Pad3)") (class "Default")
      (node (ref "RELAY5") (pin "3") (pinfunction "3_3") (pintype "unspecified"))
      (node (ref "U12") (pin "1") (pinfunction "1_1") (pintype "unspecified"))
    )
    (net (code "89") (name "Net-(RELAY6-Pad2)") (class "Default")
      (node (ref "RELAY6") (pin "2") (pinfunction "2_2") (pintype "unspecified"))
      (node (ref "U13") (pin "2") (pinfunction "2_2") (pintype "unspecified"))
    )
    (net (code "90") (name "Net-(RELAY6-Pad3)") (class "Default")
      (node (ref "RELAY6") (pin "3") (pinfunction "3_3") (pintype "unspecified"))
      (node (ref "U13") (pin "1") (pinfunction "1_1") (pintype "unspecified"))
    )
    (net (code "91") (name "Net-(RELAY7-Pad2)") (class "Default")
      (node (ref "RELAY7") (pin "2") (pinfunction "2_2") (pintype "unspecified"))
      (node (ref "U14") (pin "2") (pinfunction "2_2") (pintype "unspecified"))
    )
    (net (code "92") (name "Net-(RELAY7-Pad3)") (class "Default")
      (node (ref "RELAY7") (pin "3") (pinfunction "3_3") (pintype "unspecified"))
      (node (ref "U14") (pin "1") (pinfunction "1_1") (pintype "unspecified"))
    )
    (net (code "93") (name "Net-(RELAY8-Pad2)") (class "Default")
      (node (ref "RELAY8") (pin "2") (pinfunction "2_2") (pintype "unspecified"))
      (node (ref "U15") (pin "2") (pinfunction "2_2") (pintype "unspecified"))
    )
    (net (code "94") (name "Net-(RELAY8-Pad3)") (class "Default")
      (node (ref "RELAY8") (pin "3") (pinfunction "3_3") (pintype "unspecified"))
      (node (ref "U15") (pin "1") (pinfunction "1_1") (pintype "unspecified"))
    )
    (net (code "95") (name "PICO_3v3") (class "Default")
      (node (ref "U9") (pin "36") (pinfunction "3V3_OUT_36") (pintype "unspecified"))
    )
    (net (code "96") (name "RESET") (class "Default")
      (node (ref "J3") (pin "1") (pinfunction "1_1") (pintype "unspecified"))
      (node (ref "RESET1") (pin "3") (pinfunction "3_3") (pintype "input"))
      (node (ref "U9") (pin "30") (pinfunction "RUN_30") (pintype "unspecified"))
    )
    (net (code "97") (name "RESET_G") (class "Default")
      (node (ref "J3") (pin "2") (pinfunction "2_2") (pintype "unspecified"))
      (node (ref "RESET1") (pin "1") (pinfunction "1_1") (pintype "input"))
      (node (ref "U9") (pin "28") (pinfunction "GND_28") (pintype "unspecified"))
    )
    (net (code "98") (name "V+A") (class "Default")
      (node (ref "CN1") (pin "3") (pinfunction "3_3") (pintype "unspecified"))
      (node (ref "H1") (pin "2") (pinfunction "2_2") (pintype "unspecified"))
    )
    (net (code "99") (name "V+B") (class "Default")
      (node (ref "CN1") (pin "4") (pinfunction "4_4") (pintype "unspecified"))
      (node (ref "H2") (pin "2") (pinfunction "2_2") (pintype "unspecified"))
    )
    (net (code "100") (name "VCC") (class "Default")
      (node (ref "C2") (pin "2") (pinfunction "2_2") (pintype "unspecified"))
      (node (ref "C3") (pin "1") (pinfunction "1_1") (pintype "unspecified"))
      (node (ref "C4") (pin "2") (pinfunction "2_2") (pintype "unspecified"))
      (node (ref "C5") (pin "2") (pinfunction "2_2") (pintype "unspecified"))
      (node (ref "C9") (pin "2") (pinfunction "2_2") (pintype "unspecified"))
      (node (ref "D9") (pin "1") (pinfunction "K_1") (pintype "unspecified"))
      (node (ref "R31") (pin "1") (pinfunction "1_1") (pintype "input"))
      (node (ref "U3") (pin "1") (pinfunction "IN_1") (pintype "passive"))
      (node (ref "U4") (pin "1") (pinfunction "IN_1") (pintype "passive"))
      (node (ref "U5") (pin "3") (pinfunction "VIN_3") (pintype "passive"))
      (node (ref "U6") (pin "3") (pinfunction "VIN_3") (pintype "passive"))
    )
    (net (code "101") (name "unconnected-(RESET1-Pad2)") (class "Default")
      (node (ref "RESET1") (pin "2") (pinfunction "2_2") (pintype "input"))
    )
    (net (code "102") (name "unconnected-(RESET1-Pad4)") (class "Default")
      (node (ref "RESET1") (pin "4") (pinfunction "4_4") (pintype "input"))
    )
    (net (code "103") (name "unconnected-(U9-3V3_EN-Pad37)") (class "Default")
      (node (ref "U9") (pin "37") (pinfunction "3V3_EN_37") (pintype "unspecified"))
    )
    (net (code "104") (name "unconnected-(U9-ADC_VREF-Pad35)") (class "Default")
      (node (ref "U9") (pin "35") (pinfunction "ADC_VREF_35") (pintype "unspecified"))
    )
    (net (code "105") (name "unconnected-(U9-AGND-Pad33)") (class "Default")
      (node (ref "U9") (pin "33") (pinfunction "AGND_33") (pintype "unspecified"))
    )
    (net (code "106") (name "unconnected-(U9-GND-Pad3)") (class "Default")
      (node (ref "U9") (pin "3") (pinfunction "GND_3") (pintype "unspecified"))
    )
    (net (code "107") (name "unconnected-(U9-GND-Pad8)") (class "Default")
      (node (ref "U9") (pin "8") (pinfunction "GND_8") (pintype "unspecified"))
    )
    (net (code "108") (name "unconnected-(U9-GND-Pad13)") (class "Default")
      (node (ref "U9") (pin "13") (pinfunction "GND_13") (pintype "unspecified"))
    )
    (net (code "109") (name "unconnected-(U9-GND-Pad18)") (class "Default")
      (node (ref "U9") (pin "18") (pinfunction "GND_18") (pintype "unspecified"))
    )
    (net (code "110") (name "unconnected-(U9-GND-Pad23)") (class "Default")
      (node (ref "U9") (pin "23") (pinfunction "GND_23") (pintype "unspecified"))
    )
    (net (code "111") (name "unconnected-(U9-VSYS-Pad39)") (class "Default")
      (node (ref "U9") (pin "39") (pinfunction "VSYS_39") (pintype "unspecified"))
    )
  )
)
